# Keg_Cop_-_Daisy_Chain_Screw.net
KiCad netlist of a schematic drawn in EAGLE
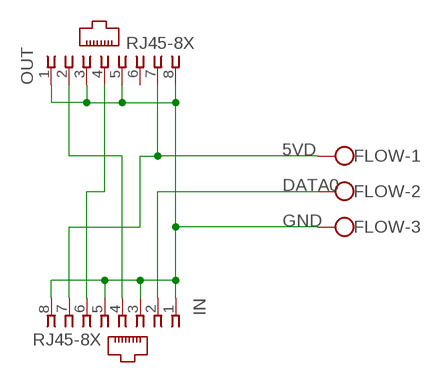
[diagram p0: schematic, sheet 1]

(export (version "E")
  (design (tool "Eeschema 10.0.6"))
  (components
    (comp (ref "FLOW")
      (value "W237-103")
      (footprint "eagle-import:W237-103")
      (fields (field (name "MPN") "237-103"))
      (libsource (lib "eagle-import") (part "W237-103"))
    )
    (comp (ref "IN")
      (value "RJ45-8X")
      (footprint "eagle-import:RJ45-NO-SHIELD")
      (libsource (lib "eagle-import") (part "RJ45-8X"))
    )
    (comp (ref "OUT")
      (value "RJ45-8X")
      (footprint "eagle-import:RJ45-NO-SHIELD")
      (libsource (lib "eagle-import") (part "RJ45-8X"))
    )
  )
  (nets
    (net (code "1") (name "/5VD") (class "Default")
      (node (ref "FLOW") (pin "1") (pinfunction "KL_1") (pintype "passive"))
      (node (ref "IN") (pin "7") (pinfunction "7_7") (pintype "passive"))
      (node (ref "OUT") (pin "7") (pinfunction "7_7") (pintype "passive"))
    )
    (net (code "2") (name "/DATA0") (class "Default")
      (node (ref "FLOW") (pin "2") (pinfunction "KL_2") (pintype "passive"))
      (node (ref "IN") (pin "2") (pinfunction "2_2") (pintype "passive"))
    )
    (net (code "3") (name "/GND") (class "Default")
      (node (ref "FLOW") (pin "3") (pinfunction "KL_3") (pintype "passive"))
      (node (ref "IN") (pin "1") (pinfunction "1_1") (pintype "passive"))
      (node (ref "IN") (pin "3") (pinfunction "3_3") (pintype "passive"))
      (node (ref "IN") (pin "5") (pinfunction "5_5") (pintype "passive"))
      (node (ref "IN") (pin "8") (pinfunction "8_8") (pintype "passive"))
      (node (ref "OUT") (pin "1") (pinfunction "1_1") (pintype "passive"))
      (node (ref "OUT") (pin "3") (pinfunction "3_3") (pintype "passive"))
      (node (ref "OUT") (pin "5") (pinfunction "5_5") (pintype "passive"))
      (node (ref "OUT") (pin "8") (pinfunction "8_8") (pintype "passive"))
    )
    (net (code "4") (name "Net-(IN-Pad4)") (class "Default")
      (node (ref "IN") (pin "4") (pinfunction "4_4") (pintype "passive"))
      (node (ref "OUT") (pin "2") (pinfunction "2_2") (pintype "passive"))
    )
    (net (code "5") (name "Net-(IN-Pad6)") (class "Default")
      (node (ref "IN") (pin "6") (pinfunction "6_6") (pintype "passive"))
      (node (ref "OUT") (pin "4") (pinfunction "4_4") (pintype "passive"))
    )
    (net (code "6") (name "unconnected-(OUT-Pad6)") (class "Default")
      (node (ref "OUT") (pin "6") (pinfunction "6_6") (pintype "passive"))
    )
  )
)
